# I2C_SENSOR.net
KiCad netlist of a schematic drawn in Altium Designer
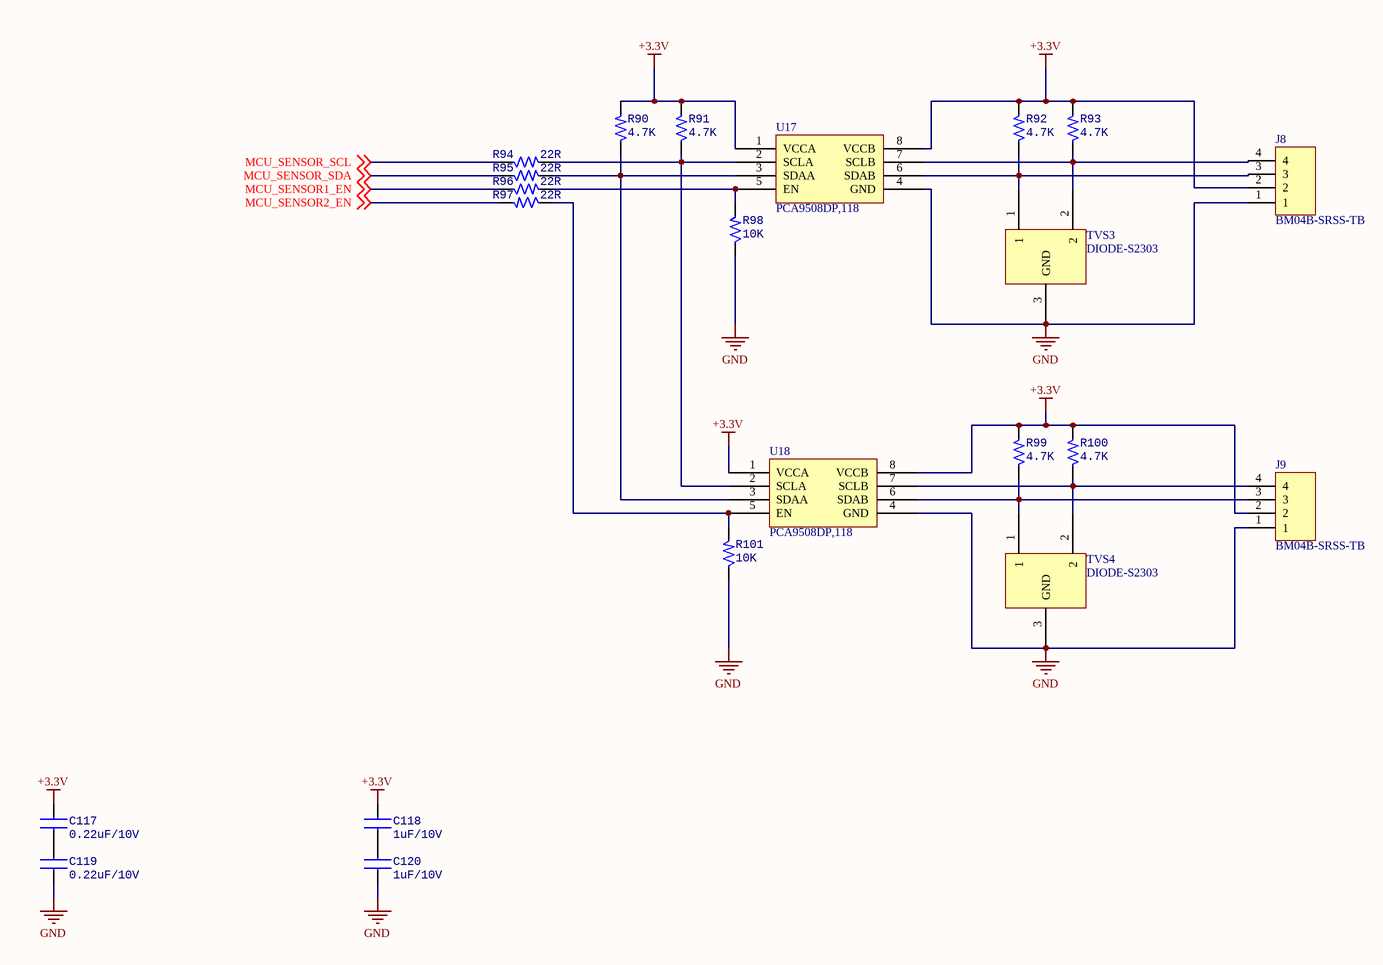
[diagram p0: I2C_SENSOR.SchDoc]

(export (version "E")
  (design (tool "Eeschema 10.0.6"))
  (components
    (comp (ref "C117")
      (value "0.22uF/10V")
      (footprint "CAP-CER-0603")
      (libsource (lib "ID") (part "CAP-CER"))
    )
    (comp (ref "C118") (value "1uF/10V") (footprint "CAP-CER-0603") (libsource (lib "ID") (part "CAP-CER")))
    (comp (ref "C119")
      (value "0.22uF/10V")
      (footprint "CAP-CER-0603")
      (libsource (lib "ID") (part "CAP-CER"))
    )
    (comp (ref "C120") (value "1uF/10V") (footprint "CAP-CER-0603") (libsource (lib "ID") (part "CAP-CER")))
    (comp (ref "J8")
      (value "BM04B-SRSS-TB")
      (footprint "BM04B-SRSS-TB")
      (description "4 Pins, 1 Row 1.25mm Pitch, right angle Connector, male")
      (fields (field (name "MANUFACTURER") "WE") (field (name "MANUFACTURER PART NUMBER") "653104131822"))
      (libsource (lib "Connector") (part "CON-PLG_4X1-50-RA-SMD"))
    )
    (comp (ref "J9")
      (value "BM04B-SRSS-TB")
      (footprint "BM04B-SRSS-TB")
      (description "4 Pins, 1 Row 1.25mm Pitch, right angle Connector, male")
      (fields (field (name "MANUFACTURER") "WE") (field (name "MANUFACTURER PART NUMBER") "653104131822"))
      (libsource (lib "Connector") (part "CON-PLG_4X1-50-RA-SMD"))
    )
    (comp (ref "R90") (value "4.7K") (footprint "RES-SMD-0603") (libsource (lib "ID") (part "RES-SMD")))
    (comp (ref "R91") (value "4.7K") (footprint "RES-SMD-0603") (libsource (lib "ID") (part "RES-SMD")))
    (comp (ref "R92") (value "4.7K") (footprint "RES-SMD-0603") (libsource (lib "ID") (part "RES-SMD")))
    (comp (ref "R93") (value "4.7K") (footprint "RES-SMD-0603") (libsource (lib "ID") (part "RES-SMD")))
    (comp (ref "R94") (value "22R") (footprint "RES-SMD-0603") (libsource (lib "ID") (part "RES-SMD")))
    (comp (ref "R95") (value "22R") (footprint "RES-SMD-0603") (libsource (lib "ID") (part "RES-SMD")))
    (comp (ref "R96") (value "22R") (footprint "RES-SMD-0603") (libsource (lib "ID") (part "RES-SMD")))
    (comp (ref "R97") (value "22R") (footprint "RES-SMD-0603") (libsource (lib "ID") (part "RES-SMD")))
    (comp (ref "R98") (value "10K") (footprint "RES-SMD-0603") (libsource (lib "ID") (part "RES-SMD")))
    (comp (ref "R99") (value "4.7K") (footprint "RES-SMD-0603") (libsource (lib "ID") (part "RES-SMD")))
    (comp (ref "R100") (value "4.7K") (footprint "RES-SMD-0603") (libsource (lib "ID") (part "RES-SMD")))
    (comp (ref "R101") (value "10K") (footprint "RES-SMD-0603") (libsource (lib "ID") (part "RES-SMD")))
    (comp (ref "TVS3")
      (value "DIODE-S2303")
      (footprint "DIODE SOT23")
      (libsource (lib "LAB_B3_209_V1") (part "DIODE-S2303"))
    )
    (comp (ref "TVS4")
      (value "DIODE-S2303")
      (footprint "DIODE SOT23")
      (libsource (lib "LAB_B3_209_V1") (part "DIODE-S2303"))
    )
    (comp (ref "U17")
      (value "PCA9508DP,118")
      (footprint "PCA9508DP,118")
      (libsource (lib "LAB_B3_209_V1") (part "PCA9508DP,118"))
    )
    (comp (ref "U18")
      (value "PCA9508DP,118")
      (footprint "PCA9508DP,118")
      (libsource (lib "LAB_B3_209_V1") (part "PCA9508DP,118"))
    )
  )
  (nets
    (net (code "1") (name "+3.3V") (class "Default")
      (node (ref "C117") (pin "1") (pinfunction "1_1") (pintype "passive"))
      (node (ref "C118") (pin "1") (pinfunction "1_1") (pintype "passive"))
      (node (ref "J8") (pin "2") (pinfunction "2_2") (pintype "passive"))
      (node (ref "J9") (pin "2") (pinfunction "2_2") (pintype "passive"))
      (node (ref "R100") (pin "2") (pinfunction "2_2") (pintype "passive"))
      (node (ref "R90") (pin "2") (pinfunction "2_2") (pintype "passive"))
      (node (ref "R91") (pin "2") (pinfunction "2_2") (pintype "passive"))
      (node (ref "R92") (pin "2") (pinfunction "2_2") (pintype "passive"))
      (node (ref "R93") (pin "2") (pinfunction "2_2") (pintype "passive"))
      (node (ref "R99") (pin "2") (pinfunction "2_2") (pintype "passive"))
      (node (ref "U17") (pin "1") (pinfunction "VCCA_1") (pintype "passive"))
      (node (ref "U17") (pin "8") (pinfunction "VCCB_8") (pintype "passive"))
      (node (ref "U18") (pin "1") (pinfunction "VCCA_1") (pintype "passive"))
      (node (ref "U18") (pin "8") (pinfunction "VCCB_8") (pintype "passive"))
    )
    (net (code "2") (name "GND") (class "Default")
      (node (ref "C119") (pin "2") (pinfunction "2_2") (pintype "passive"))
      (node (ref "C120") (pin "2") (pinfunction "2_2") (pintype "passive"))
      (node (ref "J8") (pin "1") (pinfunction "1_1") (pintype "passive"))
      (node (ref "J9") (pin "1") (pinfunction "1_1") (pintype "passive"))
      (node (ref "R101") (pin "1") (pinfunction "1_1") (pintype "passive"))
      (node (ref "R98") (pin "1") (pinfunction "1_1") (pintype "passive"))
      (node (ref "TVS3") (pin "3") (pinfunction "GND_3") (pintype "passive"))
      (node (ref "TVS4") (pin "3") (pinfunction "GND_3") (pintype "passive"))
      (node (ref "U17") (pin "4") (pinfunction "GND_4") (pintype "passive"))
      (node (ref "U18") (pin "4") (pinfunction "GND_4") (pintype "passive"))
    )
    (net (code "3") (name "MCU_SENSOR1_EN") (class "Default")
      (node (ref "R96") (pin "1") (pinfunction "1_1") (pintype "passive"))
    )
    (net (code "4") (name "MCU_SENSOR2_EN") (class "Default")
      (node (ref "R97") (pin "2") (pinfunction "2_2") (pintype "passive"))
    )
    (net (code "5") (name "MCU_SENSOR_SCL") (class "Default")
      (node (ref "R94") (pin "1") (pinfunction "1_1") (pintype "passive"))
    )
    (net (code "6") (name "MCU_SENSOR_SDA") (class "Default")
      (node (ref "R95") (pin "1") (pinfunction "1_1") (pintype "passive"))
    )
    (net (code "7") (name "Net-(C117-Pad2)") (class "Default")
      (node (ref "C117") (pin "2") (pinfunction "2_2") (pintype "passive"))
      (node (ref "C119") (pin "1") (pinfunction "1_1") (pintype "passive"))
    )
    (net (code "8") (name "Net-(C118-Pad2)") (class "Default")
      (node (ref "C118") (pin "2") (pinfunction "2_2") (pintype "passive"))
      (node (ref "C120") (pin "1") (pinfunction "1_1") (pintype "passive"))
    )
    (net (code "9") (name "Net-(U17-EN)") (class "Default")
      (node (ref "R96") (pin "2") (pinfunction "2_2") (pintype "passive"))
      (node (ref "R98") (pin "2") (pinfunction "2_2") (pintype "passive"))
      (node (ref "U17") (pin "5") (pinfunction "EN_5") (pintype "passive"))
    )
    (net (code "10") (name "Net-(U17-SCLA)") (class "Default")
      (node (ref "R91") (pin "1") (pinfunction "1_1") (pintype "passive"))
      (node (ref "R94") (pin "2") (pinfunction "2_2") (pintype "passive"))
      (node (ref "U17") (pin "2") (pinfunction "SCLA_2") (pintype "passive"))
      (node (ref "U18") (pin "2") (pinfunction "SCLA_2") (pintype "passive"))
    )
    (net (code "11") (name "Net-(U17-SCLB)") (class "Default")
      (node (ref "J8") (pin "4") (pinfunction "4_4") (pintype "passive"))
      (node (ref "R93") (pin "1") (pinfunction "1_1") (pintype "passive"))
      (node (ref "TVS3") (pin "2") (pinfunction "2_2") (pintype "passive"))
      (node (ref "U17") (pin "7") (pinfunction "SCLB_7") (pintype "passive"))
    )
    (net (code "12") (name "Net-(U17-SDAA)") (class "Default")
      (node (ref "R90") (pin "1") (pinfunction "1_1") (pintype "passive"))
      (node (ref "R95") (pin "2") (pinfunction "2_2") (pintype "passive"))
      (node (ref "U17") (pin "3") (pinfunction "SDAA_3") (pintype "passive"))
      (node (ref "U18") (pin "3") (pinfunction "SDAA_3") (pintype "passive"))
    )
    (net (code "13") (name "Net-(U17-SDAB)") (class "Default")
      (node (ref "J8") (pin "3") (pinfunction "3_3") (pintype "passive"))
      (node (ref "R92") (pin "1") (pinfunction "1_1") (pintype "passive"))
      (node (ref "TVS3") (pin "1") (pinfunction "1_1") (pintype "passive"))
      (node (ref "U17") (pin "6") (pinfunction "SDAB_6") (pintype "passive"))
    )
    (net (code "14") (name "Net-(U18-EN)") (class "Default")
      (node (ref "R101") (pin "2") (pinfunction "2_2") (pintype "passive"))
      (node (ref "R97") (pin "1") (pinfunction "1_1") (pintype "passive"))
      (node (ref "U18") (pin "5") (pinfunction "EN_5") (pintype "passive"))
    )
    (net (code "15") (name "Net-(U18-SCLB)") (class "Default")
      (node (ref "J9") (pin "4") (pinfunction "4_4") (pintype "passive"))
      (node (ref "R100") (pin "1") (pinfunction "1_1") (pintype "passive"))
      (node (ref "TVS4") (pin "2") (pinfunction "2_2") (pintype "passive"))
      (node (ref "U18") (pin "7") (pinfunction "SCLB_7") (pintype "passive"))
    )
    (net (code "16") (name "Net-(U18-SDAB)") (class "Default")
      (node (ref "J9") (pin "3") (pinfunction "3_3") (pintype "passive"))
      (node (ref "R99") (pin "1") (pinfunction "1_1") (pintype "passive"))
      (node (ref "TVS4") (pin "1") (pinfunction "1_1") (pintype "passive"))
      (node (ref "U18") (pin "6") (pinfunction "SDAB_6") (pintype "passive"))
    )
  )
)
